# 2_power.net
KiCad netlist of a schematic drawn in Altium Designer
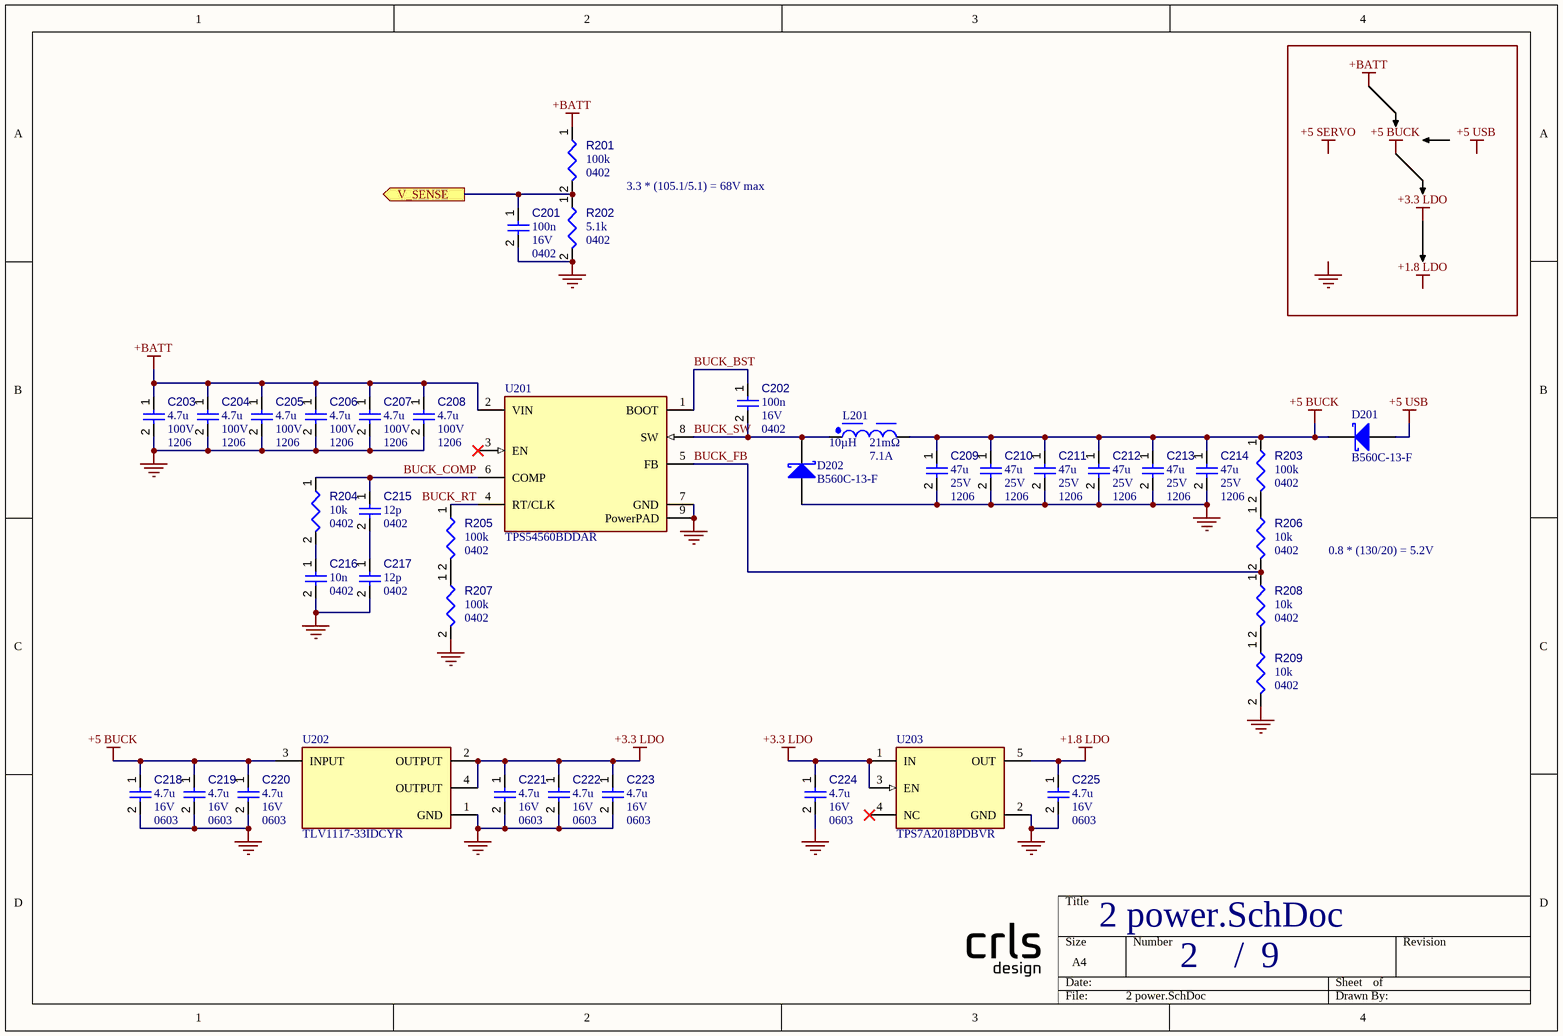
[diagram p0: 2 power.SchDoc]

(export (version "E")
  (design (tool "Eeschema 10.0.6"))
  (components
    (comp (ref "C201")
      (value "100n")
      (footprint "CAPC0402(1005)60_L")
      (description "Capacitor")
      (fields
        (field (name "CASE/PACKAGE") "0402")
        (field (name "VOLTAGE RATING") "16V")
        (field (name "Comment") "Capacitors,0402,100n,16V")
      )
      (libsource (lib "UBC Uncrewed Aircraft Systems") (part "CAP-NP-2"))
    )
    (comp (ref "C202")
      (value "100n")
      (footprint "CAPC0402(1005)60_L")
      (description "Capacitor")
      (fields
        (field (name "CASE/PACKAGE") "0402")
        (field (name "VOLTAGE RATING") "16V")
        (field (name "Comment") "Capacitors,0402,100n,16V")
      )
      (libsource (lib "UBC Uncrewed Aircraft Systems") (part "CAP-NP-2"))
    )
    (comp (ref "C203")
      (value "4.7u")
      (footprint "CAPC3216X180X50NL20T25")
      (description "Capacitor")
      (fields
        (field (name "CASE/PACKAGE") "1206")
        (field (name "VOLTAGE RATING") "100V")
        (field (name "Comment") "Capacitors,1206,4.7u,100V")
      )
      (libsource (lib "UBC Uncrewed Aircraft Systems") (part "CAP-NP-2"))
    )
    (comp (ref "C204")
      (value "4.7u")
      (footprint "CAPC3216X180X50NL20T25")
      (description "Capacitor")
      (fields
        (field (name "CASE/PACKAGE") "1206")
        (field (name "VOLTAGE RATING") "100V")
        (field (name "Comment") "Capacitors,1206,4.7u,100V")
      )
      (libsource (lib "UBC Uncrewed Aircraft Systems") (part "CAP-NP-2"))
    )
    (comp (ref "C205")
      (value "4.7u")
      (footprint "CAPC3216X180X50NL20T25")
      (description "Capacitor")
      (fields
        (field (name "CASE/PACKAGE") "1206")
        (field (name "VOLTAGE RATING") "100V")
        (field (name "Comment") "Capacitors,1206,4.7u,100V")
      )
      (libsource (lib "UBC Uncrewed Aircraft Systems") (part "CAP-NP-2"))
    )
    (comp (ref "C206")
      (value "4.7u")
      (footprint "CAPC3216X180X50NL20T25")
      (description "Capacitor")
      (fields
        (field (name "CASE/PACKAGE") "1206")
        (field (name "VOLTAGE RATING") "100V")
        (field (name "Comment") "Capacitors,1206,4.7u,100V")
      )
      (libsource (lib "UBC Uncrewed Aircraft Systems") (part "CAP-NP-2"))
    )
    (comp (ref "C207")
      (value "4.7u")
      (footprint "CAPC3216X180X50NL20T25")
      (description "Capacitor")
      (fields
        (field (name "CASE/PACKAGE") "1206")
        (field (name "VOLTAGE RATING") "100V")
        (field (name "Comment") "Capacitors,1206,4.7u,100V")
      )
      (libsource (lib "UBC Uncrewed Aircraft Systems") (part "CAP-NP-2"))
    )
    (comp (ref "C208")
      (value "4.7u")
      (footprint "CAPC3216X180X50NL20T25")
      (description "Capacitor")
      (fields
        (field (name "CASE/PACKAGE") "1206")
        (field (name "VOLTAGE RATING") "100V")
        (field (name "Comment") "Capacitors,1206,4.7u,100V")
      )
      (libsource (lib "UBC Uncrewed Aircraft Systems") (part "CAP-NP-2"))
    )
    (comp (ref "C209")
      (value "47u")
      (footprint "CAPC3216X180X50NL20T25")
      (description "Capacitor")
      (fields
        (field (name "CASE/PACKAGE") "1206")
        (field (name "VOLTAGE RATING") "25V")
        (field (name "Comment") "Capacitors,1206,47u,25V")
      )
      (libsource (lib "UBC Uncrewed Aircraft Systems") (part "CAP-NP-2"))
    )
    (comp (ref "C210")
      (value "47u")
      (footprint "CAPC3216X180X50NL20T25")
      (description "Capacitor")
      (fields
        (field (name "CASE/PACKAGE") "1206")
        (field (name "VOLTAGE RATING") "25V")
        (field (name "Comment") "Capacitors,1206,47u,25V")
      )
      (libsource (lib "UBC Uncrewed Aircraft Systems") (part "CAP-NP-2"))
    )
    (comp (ref "C211")
      (value "47u")
      (footprint "CAPC3216X180X50NL20T25")
      (description "Capacitor")
      (fields
        (field (name "CASE/PACKAGE") "1206")
        (field (name "VOLTAGE RATING") "25V")
        (field (name "Comment") "Capacitors,1206,47u,25V")
      )
      (libsource (lib "UBC Uncrewed Aircraft Systems") (part "CAP-NP-2"))
    )
    (comp (ref "C212")
      (value "47u")
      (footprint "CAPC3216X180X50NL20T25")
      (description "Capacitor")
      (fields
        (field (name "CASE/PACKAGE") "1206")
        (field (name "VOLTAGE RATING") "25V")
        (field (name "Comment") "Capacitors,1206,47u,25V")
      )
      (libsource (lib "UBC Uncrewed Aircraft Systems") (part "CAP-NP-2"))
    )
    (comp (ref "C213")
      (value "47u")
      (footprint "CAPC3216X180X50NL20T25")
      (description "Capacitor")
      (fields
        (field (name "CASE/PACKAGE") "1206")
        (field (name "VOLTAGE RATING") "25V")
        (field (name "Comment") "Capacitors,1206,47u,25V")
      )
      (libsource (lib "UBC Uncrewed Aircraft Systems") (part "CAP-NP-2"))
    )
    (comp (ref "C214")
      (value "47u")
      (footprint "CAPC3216X180X50NL20T25")
      (description "Capacitor")
      (fields
        (field (name "CASE/PACKAGE") "1206")
        (field (name "VOLTAGE RATING") "25V")
        (field (name "Comment") "Capacitors,1206,47u,25V")
      )
      (libsource (lib "UBC Uncrewed Aircraft Systems") (part "CAP-NP-2"))
    )
    (comp (ref "C215")
      (value "12p")
      (footprint "CAPC0402(1005)60_L")
      (description "Capacitor")
      (fields (field (name "CASE/PACKAGE") "0402") (field (name "Comment") "Capacitors,0402,12p"))
      (libsource (lib "UBC Uncrewed Aircraft Systems") (part "CAP-NP-2"))
    )
    (comp (ref "C216")
      (value "10n")
      (footprint "CAPC0402(1005)60_L")
      (description "Capacitor")
      (fields (field (name "CASE/PACKAGE") "0402") (field (name "Comment") "Capacitors,0402,10n"))
      (libsource (lib "UBC Uncrewed Aircraft Systems") (part "CAP-NP-2"))
    )
    (comp (ref "C217")
      (value "12p")
      (footprint "CAPC0402(1005)60_L")
      (description "Capacitor")
      (fields (field (name "CASE/PACKAGE") "0402") (field (name "Comment") "Capacitors,0402,12p"))
      (libsource (lib "UBC Uncrewed Aircraft Systems") (part "CAP-NP-2"))
    )
    (comp (ref "C218")
      (value "4.7u")
      (footprint "CAPC0603(1608)100_L")
      (description "Capacitor")
      (fields
        (field (name "CASE/PACKAGE") "0603")
        (field (name "VOLTAGE RATING") "16V")
        (field (name "Comment") "Capacitors,0603,4.7u,16V")
      )
      (libsource (lib "UBC Uncrewed Aircraft Systems") (part "CAP-NP-2"))
    )
    (comp (ref "C219")
      (value "4.7u")
      (footprint "CAPC0603(1608)100_L")
      (description "Capacitor")
      (fields
        (field (name "CASE/PACKAGE") "0603")
        (field (name "VOLTAGE RATING") "16V")
        (field (name "Comment") "Capacitors,0603,4.7u,16V")
      )
      (libsource (lib "UBC Uncrewed Aircraft Systems") (part "CAP-NP-2"))
    )
    (comp (ref "C220")
      (value "4.7u")
      (footprint "CAPC0603(1608)100_L")
      (description "Capacitor")
      (fields
        (field (name "CASE/PACKAGE") "0603")
        (field (name "VOLTAGE RATING") "16V")
        (field (name "Comment") "Capacitors,0603,4.7u,16V")
      )
      (libsource (lib "UBC Uncrewed Aircraft Systems") (part "CAP-NP-2"))
    )
    (comp (ref "C221")
      (value "4.7u")
      (footprint "CAPC0603(1608)100_L")
      (description "Capacitor")
      (fields
        (field (name "CASE/PACKAGE") "0603")
        (field (name "VOLTAGE RATING") "16V")
        (field (name "Comment") "Capacitors,0603,4.7u,16V")
      )
      (libsource (lib "UBC Uncrewed Aircraft Systems") (part "CAP-NP-2"))
    )
    (comp (ref "C222")
      (value "4.7u")
      (footprint "CAPC0603(1608)100_L")
      (description "Capacitor")
      (fields
        (field (name "CASE/PACKAGE") "0603")
        (field (name "VOLTAGE RATING") "16V")
        (field (name "Comment") "Capacitors,0603,4.7u,16V")
      )
      (libsource (lib "UBC Uncrewed Aircraft Systems") (part "CAP-NP-2"))
    )
    (comp (ref "C223")
      (value "4.7u")
      (footprint "CAPC0603(1608)100_L")
      (description "Capacitor")
      (fields
        (field (name "CASE/PACKAGE") "0603")
        (field (name "VOLTAGE RATING") "16V")
        (field (name "Comment") "Capacitors,0603,4.7u,16V")
      )
      (libsource (lib "UBC Uncrewed Aircraft Systems") (part "CAP-NP-2"))
    )
    (comp (ref "C224")
      (value "4.7u")
      (footprint "CAPC0603(1608)100_L")
      (description "Capacitor")
      (fields
        (field (name "CASE/PACKAGE") "0603")
        (field (name "VOLTAGE RATING") "16V")
        (field (name "Comment") "Capacitors,0603,4.7u,16V")
      )
      (libsource (lib "UBC Uncrewed Aircraft Systems") (part "CAP-NP-2"))
    )
    (comp (ref "C225")
      (value "4.7u")
      (footprint "CAPC0603(1608)100_L")
      (description "Capacitor")
      (fields
        (field (name "CASE/PACKAGE") "0603")
        (field (name "VOLTAGE RATING") "16V")
        (field (name "Comment") "Capacitors,0603,4.7u,16V")
      )
      (libsource (lib "UBC Uncrewed Aircraft Systems") (part "CAP-NP-2"))
    )
    (comp (ref "D201")
      (value "B560C-13-F")
      (footprint "DIOD-B5X0C-2_N")
      (description "Schottky Barrier Rectifier, 5 A, 60 V, -55 to 125 degC, 2-Pin SMD, RoHS, Tape and Reel")
      (fields (field (name "MANUFACTURER") "DiodesIncorporated"))
      (libsource (lib "Altium Content Vault") (part "DSKY-KA-2"))
    )
    (comp (ref "D202")
      (value "B560C-13-F")
      (footprint "DIOD-B5X0C-2_N")
      (description "Schottky Barrier Rectifier, 5 A, 60 V, -55 to 125 degC, 2-Pin SMD, RoHS, Tape and Reel")
      (fields (field (name "MANUFACTURER") "DiodesIncorporated"))
      (libsource (lib "Altium Content Vault") (part "DSKY-KA-2"))
    )
    (comp (ref "L201")
      (value "7447709100")
      (footprint "WE-PD_1210")
      (fields
        (field (name "MAX DC CURRENT") "7.1A")
        (field (name "SERIES RESISTANCE") "21mΩ")
        (field (name "INDUCTANCE") "10µH")
        (field (name "TOLERANCE") "20%")
      )
      (libsource (lib "Altium Content Vault") (part "Inductor - 2"))
    )
    (comp (ref "R201")
      (value "100k")
      (footprint "RESC0402(1005)_L")
      (description "Resistor")
      (fields
        (field (name "CASE/PACKAGE") "0402")
        (field (name "TOLERANCE") "1%")
        (field (name "Comment") "Resistors,0402,1%,100k")
      )
      (libsource (lib "UBC Uncrewed Aircraft Systems") (part "RES-2"))
    )
    (comp (ref "R202")
      (value "5.1k")
      (footprint "RESC0402(1005)_L")
      (description "Resistor")
      (fields
        (field (name "CASE/PACKAGE") "0402")
        (field (name "TOLERANCE") "1%")
        (field (name "Comment") "Resistors,0402,1%,5.1k")
      )
      (libsource (lib "UBC Uncrewed Aircraft Systems") (part "RES-2"))
    )
    (comp (ref "R203")
      (value "100k")
      (footprint "RESC0402(1005)_L")
      (description "Resistor")
      (fields
        (field (name "CASE/PACKAGE") "0402")
        (field (name "TOLERANCE") "1%")
        (field (name "Comment") "Resistors,0402,1%,100k")
      )
      (libsource (lib "UBC Uncrewed Aircraft Systems") (part "RES-2"))
    )
    (comp (ref "R204")
      (value "10k")
      (footprint "RESC0402(1005)_L")
      (description "Resistor")
      (fields
        (field (name "CASE/PACKAGE") "0402")
        (field (name "TOLERANCE") "1%")
        (field (name "Comment") "Resistors,0402,1%,10k")
      )
      (libsource (lib "UBC Uncrewed Aircraft Systems") (part "RES-2"))
    )
    (comp (ref "R205")
      (value "100k")
      (footprint "RESC0402(1005)_L")
      (description "Resistor")
      (fields
        (field (name "CASE/PACKAGE") "0402")
        (field (name "TOLERANCE") "1%")
        (field (name "Comment") "Resistors,0402,1%,100k")
      )
      (libsource (lib "UBC Uncrewed Aircraft Systems") (part "RES-2"))
    )
    (comp (ref "R206")
      (value "10k")
      (footprint "RESC0402(1005)_L")
      (description "Resistor")
      (fields
        (field (name "CASE/PACKAGE") "0402")
        (field (name "TOLERANCE") "1%")
        (field (name "Comment") "Resistors,0402,1%,10k")
      )
      (libsource (lib "UBC Uncrewed Aircraft Systems") (part "RES-2"))
    )
    (comp (ref "R207")
      (value "100k")
      (footprint "RESC0402(1005)_L")
      (description "Resistor")
      (fields
        (field (name "CASE/PACKAGE") "0402")
        (field (name "TOLERANCE") "1%")
        (field (name "Comment") "Resistors,0402,1%,100k")
      )
      (libsource (lib "UBC Uncrewed Aircraft Systems") (part "RES-2"))
    )
    (comp (ref "R208")
      (value "10k")
      (footprint "RESC0402(1005)_L")
      (description "Resistor")
      (fields
        (field (name "CASE/PACKAGE") "0402")
        (field (name "TOLERANCE") "1%")
        (field (name "Comment") "Resistors,0402,1%,10k")
      )
      (libsource (lib "UBC Uncrewed Aircraft Systems") (part "RES-2"))
    )
    (comp (ref "R209")
      (value "10k")
      (footprint "RESC0402(1005)_L")
      (description "Resistor")
      (fields
        (field (name "CASE/PACKAGE") "0402")
        (field (name "TOLERANCE") "1%")
        (field (name "Comment") "Resistors,0402,1%,10k")
      )
      (libsource (lib "UBC Uncrewed Aircraft Systems") (part "RES-2"))
    )
    (comp (ref "U201")
      (value "TPS54560BDDAR")
      (footprint "FP-DDA0008E-IPC_C")
      (description "IC REG CTRLR")
      (libsource (lib "Altium Content Vault") (part "2f88d594a2943ea9935c3555fd74e7d"))
    )
    (comp (ref "U202")
      (value "TLV1117-33IDCYR")
      (footprint "FP-DCY0004A-MFG")
      (description "IC REG LIN 3.3V 800MA SOT223-4")
      (fields
        (field (name "MANUFACTURER") "Texas Instruments")
        (field (name "OCTOPART") "https://octopart.com/tlv1117-33idcyr-texas+instruments-669250")
      )
      (libsource (lib "Altium Content Vault") (part "d420fb9686013fb832e66295cdf4acf"))
    )
    (comp (ref "U203")
      (value "TPS7A2018PDBVR")
      (footprint "FP-DBV0005A-MFG")
      (description "IC REG LINEAR 1.8V 300MA SOT23-5")
      (libsource (lib "Altium Content Vault") (part "07e51adf658dd7550fcbd1980b41b01"))
    )
  )
  (nets
    (net (code "1") (name "+1.8 LDO") (class "Default")
      (node (ref "C225") (pin "1") (pinfunction "1_1") (pintype "passive"))
      (node (ref "U203") (pin "5") (pinfunction "OUT_5") (pintype "passive"))
    )
    (net (code "2") (name "+3.3 LDO") (class "Default")
      (node (ref "C221") (pin "1") (pinfunction "1_1") (pintype "passive"))
      (node (ref "C222") (pin "1") (pinfunction "1_1") (pintype "passive"))
      (node (ref "C223") (pin "1") (pinfunction "1_1") (pintype "passive"))
      (node (ref "C224") (pin "1") (pinfunction "1_1") (pintype "passive"))
      (node (ref "U202") (pin "2") (pinfunction "OUTPUT_2") (pintype "power_in"))
      (node (ref "U202") (pin "4") (pinfunction "OUTPUT_4") (pintype "power_in"))
      (node (ref "U203") (pin "1") (pinfunction "IN_1") (pintype "power_in"))
      (node (ref "U203") (pin "3") (pinfunction "EN_3") (pintype "input"))
    )
    (net (code "3") (name "+5 BUCK") (class "Default")
      (node (ref "C209") (pin "1") (pinfunction "1_1") (pintype "passive"))
      (node (ref "C210") (pin "1") (pinfunction "1_1") (pintype "passive"))
      (node (ref "C211") (pin "1") (pinfunction "1_1") (pintype "passive"))
      (node (ref "C212") (pin "1") (pinfunction "1_1") (pintype "passive"))
      (node (ref "C213") (pin "1") (pinfunction "1_1") (pintype "passive"))
      (node (ref "C214") (pin "1") (pinfunction "1_1") (pintype "passive"))
      (node (ref "C218") (pin "1") (pinfunction "1_1") (pintype "passive"))
      (node (ref "C219") (pin "1") (pinfunction "1_1") (pintype "passive"))
      (node (ref "C220") (pin "1") (pinfunction "1_1") (pintype "passive"))
      (node (ref "D201") (pin "1") (pinfunction "K_1") (pintype "passive"))
      (node (ref "L201") (pin "2") (pinfunction "2_2") (pintype "passive"))
      (node (ref "R203") (pin "1") (pinfunction "1_1") (pintype "passive"))
      (node (ref "U202") (pin "3") (pinfunction "INPUT_3") (pintype "power_in"))
    )
    (net (code "5") (name "+5 USB") (class "Default")
      (node (ref "D201") (pin "2") (pinfunction "A_2") (pintype "passive"))
    )
    (net (code "6") (name "+BATT") (class "Default")
      (node (ref "C203") (pin "1") (pinfunction "1_1") (pintype "passive"))
      (node (ref "C204") (pin "1") (pinfunction "1_1") (pintype "passive"))
      (node (ref "C205") (pin "1") (pinfunction "1_1") (pintype "passive"))
      (node (ref "C206") (pin "1") (pinfunction "1_1") (pintype "passive"))
      (node (ref "C207") (pin "1") (pinfunction "1_1") (pintype "passive"))
      (node (ref "C208") (pin "1") (pinfunction "1_1") (pintype "passive"))
      (node (ref "R201") (pin "1") (pinfunction "1_1") (pintype "passive"))
      (node (ref "U201") (pin "2") (pinfunction "VIN_2") (pintype "power_in"))
    )
    (net (code "7") (name "/BUCK_BST") (class "Default")
      (node (ref "C202") (pin "1") (pinfunction "1_1") (pintype "passive"))
      (node (ref "U201") (pin "1") (pinfunction "BOOT_1") (pintype "passive"))
    )
    (net (code "8") (name "/BUCK_COMP") (class "Default")
      (node (ref "C215") (pin "1") (pinfunction "1_1") (pintype "passive"))
      (node (ref "R204") (pin "1") (pinfunction "1_1") (pintype "passive"))
      (node (ref "U201") (pin "6") (pinfunction "COMP_6") (pintype "passive"))
    )
    (net (code "9") (name "/BUCK_FB") (class "Default")
      (node (ref "R206") (pin "2") (pinfunction "2_2") (pintype "passive"))
      (node (ref "R208") (pin "1") (pinfunction "1_1") (pintype "passive"))
      (node (ref "U201") (pin "5") (pinfunction "FB_5") (pintype "passive"))
    )
    (net (code "10") (name "/BUCK_RT") (class "Default")
      (node (ref "R205") (pin "1") (pinfunction "1_1") (pintype "passive"))
      (node (ref "U201") (pin "4") (pinfunction "RT/CLK_4") (pintype "passive"))
    )
    (net (code "11") (name "/BUCK_SW") (class "Default")
      (node (ref "C202") (pin "2") (pinfunction "2_2") (pintype "passive"))
      (node (ref "D202") (pin "1") (pinfunction "K_1") (pintype "passive"))
      (node (ref "L201") (pin "1") (pinfunction "1_1") (pintype "passive"))
      (node (ref "U201") (pin "8") (pinfunction "SW_8") (pintype "input"))
    )
    (net (code "12") (name "/V_SENSE") (class "Default")
      (node (ref "C201") (pin "1") (pinfunction "1_1") (pintype "passive"))
      (node (ref "R201") (pin "2") (pinfunction "2_2") (pintype "passive"))
      (node (ref "R202") (pin "1") (pinfunction "1_1") (pintype "passive"))
    )
    (net (code "13") (name "GND") (class "Default")
      (node (ref "C201") (pin "2") (pinfunction "2_2") (pintype "passive"))
      (node (ref "C203") (pin "2") (pinfunction "2_2") (pintype "passive"))
      (node (ref "C204") (pin "2") (pinfunction "2_2") (pintype "passive"))
      (node (ref "C205") (pin "2") (pinfunction "2_2") (pintype "passive"))
      (node (ref "C206") (pin "2") (pinfunction "2_2") (pintype "passive"))
      (node (ref "C207") (pin "2") (pinfunction "2_2") (pintype "passive"))
      (node (ref "C208") (pin "2") (pinfunction "2_2") (pintype "passive"))
      (node (ref "C209") (pin "2") (pinfunction "2_2") (pintype "passive"))
      (node (ref "C210") (pin "2") (pinfunction "2_2") (pintype "passive"))
      (node (ref "C211") (pin "2") (pinfunction "2_2") (pintype "passive"))
      (node (ref "C212") (pin "2") (pinfunction "2_2") (pintype "passive"))
      (node (ref "C213") (pin "2") (pinfunction "2_2") (pintype "passive"))
      (node (ref "C214") (pin "2") (pinfunction "2_2") (pintype "passive"))
      (node (ref "C216") (pin "2") (pinfunction "2_2") (pintype "passive"))
      (node (ref "C217") (pin "2") (pinfunction "2_2") (pintype "passive"))
      (node (ref "C218") (pin "2") (pinfunction "2_2") (pintype "passive"))
      (node (ref "C219") (pin "2") (pinfunction "2_2") (pintype "passive"))
      (node (ref "C220") (pin "2") (pinfunction "2_2") (pintype "passive"))
      (node (ref "C221") (pin "2") (pinfunction "2_2") (pintype "passive"))
      (node (ref "C222") (pin "2") (pinfunction "2_2") (pintype "passive"))
      (node (ref "C223") (pin "2") (pinfunction "2_2") (pintype "passive"))
      (node (ref "C224") (pin "2") (pinfunction "2_2") (pintype "passive"))
      (node (ref "C225") (pin "2") (pinfunction "2_2") (pintype "passive"))
      (node (ref "D202") (pin "2") (pinfunction "A_2") (pintype "passive"))
      (node (ref "R202") (pin "2") (pinfunction "2_2") (pintype "passive"))
      (node (ref "R207") (pin "2") (pinfunction "2_2") (pintype "passive"))
      (node (ref "R209") (pin "2") (pinfunction "2_2") (pintype "passive"))
      (node (ref "U201") (pin "7") (pinfunction "GND_7") (pintype "power_in"))
      (node (ref "U201") (pin "9") (pinfunction "PowerPAD_9") (pintype "power_in"))
      (node (ref "U202") (pin "1") (pinfunction "GND_1") (pintype "power_in"))
      (node (ref "U203") (pin "2") (pinfunction "GND_2") (pintype "power_in"))
    )
    (net (code "14") (name "Net-(C215-Pad2)") (class "Default")
      (node (ref "C215") (pin "2") (pinfunction "2_2") (pintype "passive"))
      (node (ref "C217") (pin "1") (pinfunction "1_1") (pintype "passive"))
    )
    (net (code "15") (name "Net-(C216-Pad1)") (class "Default")
      (node (ref "C216") (pin "1") (pinfunction "1_1") (pintype "passive"))
      (node (ref "R204") (pin "2") (pinfunction "2_2") (pintype "passive"))
    )
    (net (code "16") (name "Net-(R203-Pad2)") (class "Default")
      (node (ref "R203") (pin "2") (pinfunction "2_2") (pintype "passive"))
      (node (ref "R206") (pin "1") (pinfunction "1_1") (pintype "passive"))
    )
    (net (code "17") (name "Net-(R205-Pad2)") (class "Default")
      (node (ref "R205") (pin "2") (pinfunction "2_2") (pintype "passive"))
      (node (ref "R207") (pin "1") (pinfunction "1_1") (pintype "passive"))
    )
    (net (code "18") (name "Net-(R208-Pad2)") (class "Default")
      (node (ref "R208") (pin "2") (pinfunction "2_2") (pintype "passive"))
      (node (ref "R209") (pin "1") (pinfunction "1_1") (pintype "passive"))
    )
    (net (code "19") (name "unconnected-(U201-EN-Pad3)") (class "Default")
      (node (ref "U201") (pin "3") (pinfunction "EN_3") (pintype "input+no_connect"))
    )
    (net (code "20") (name "unconnected-(U203-NC-Pad4)") (class "Default")
      (node (ref "U203") (pin "4") (pinfunction "NC_4") (pintype "passive+no_connect"))
    )
  )
)
